# adapter.net
KiCad netlist of a schematic drawn in EAGLE
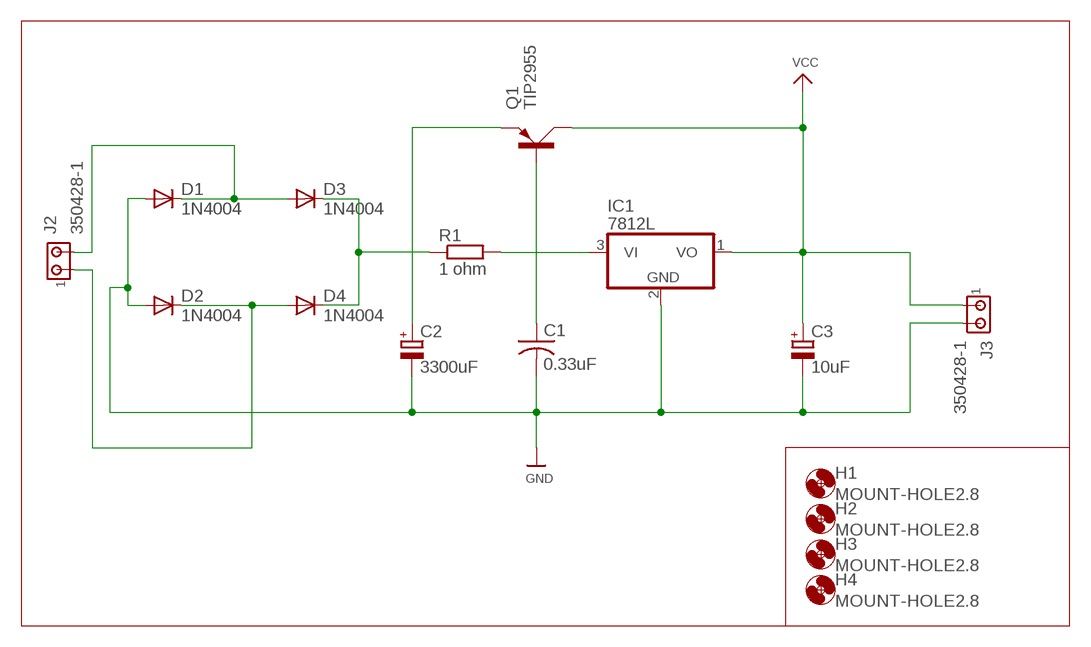
[diagram p0: schematic, sheet 1]

(export (version "E")
  (design (tool "Eeschema 10.0.6"))
  (components
    (comp (ref "C1")
      (value "0.33uF")
      (footprint "eagle-import:C025-024X044")
      (libsource (lib "eagle-import") (part "C-US025-024X044"))
    )
    (comp (ref "C2")
      (value "3300uF")
      (footprint "eagle-import:CAPPRD508W65D1000H1100B")
      (libsource (lib "eagle-import") (part "C-POLRADIAL-11MM-DIA_"))
    )
    (comp (ref "C3")
      (value "10uF")
      (footprint "eagle-import:CAPPRD508W65D1000H1100B")
      (libsource (lib "eagle-import") (part "C-POLRADIAL-11MM-DIA_"))
    )
    (comp (ref "D1")
      (value "1N4004")
      (footprint "eagle-import:DO41-10")
      (libsource (lib "eagle-import") (part "1N4004"))
    )
    (comp (ref "D2")
      (value "1N4004")
      (footprint "eagle-import:DO41-10")
      (libsource (lib "eagle-import") (part "1N4004"))
    )
    (comp (ref "D3")
      (value "1N4004")
      (footprint "eagle-import:DO41-10")
      (libsource (lib "eagle-import") (part "1N4004"))
    )
    (comp (ref "D4")
      (value "1N4004")
      (footprint "eagle-import:DO41-10")
      (libsource (lib "eagle-import") (part "1N4004"))
    )
    (comp (ref "H1")
      (value "MOUNT-HOLE2.8")
      (footprint "eagle-import:2,8")
      (libsource (lib "eagle-import") (part "MOUNT-HOLE2.8"))
    )
    (comp (ref "H2")
      (value "MOUNT-HOLE2.8")
      (footprint "eagle-import:2,8")
      (libsource (lib "eagle-import") (part "MOUNT-HOLE2.8"))
    )
    (comp (ref "H3")
      (value "MOUNT-HOLE2.8")
      (footprint "eagle-import:2,8")
      (libsource (lib "eagle-import") (part "MOUNT-HOLE2.8"))
    )
    (comp (ref "H4")
      (value "MOUNT-HOLE2.8")
      (footprint "eagle-import:2,8")
      (libsource (lib "eagle-import") (part "MOUNT-HOLE2.8"))
    )
    (comp (ref "IC1")
      (value "7812L")
      (footprint "eagle-import:TO92")
      (libsource (lib "eagle-import") (part "78L12"))
    )
    (comp (ref "J2")
      (value "350428-1")
      (footprint "eagle-import:350428-1")
      (libsource (lib "eagle-import") (part "350428-1"))
    )
    (comp (ref "J3")
      (value "350428-1")
      (footprint "eagle-import:350428-1")
      (libsource (lib "eagle-import") (part "350428-1"))
    )
    (comp (ref "Q1")
      (value "TIP2955")
      (footprint "eagle-import:TOP3AV")
      (fields (field (name "DIGIKEY_PART_NUMBER") "497-2608-5-ND") (field (name "MF") "STMicroelectronics"))
      (libsource (lib "eagle-import") (part "TIP2955"))
    )
    (comp (ref "R1")
      (value "1 ohm")
      (footprint "eagle-import:0204_7")
      (libsource (lib "eagle-import") (part "R-EU_0204/7"))
    )
  )
  (nets
    (net (code "1") (name "GND") (class "Default")
      (node (ref "C1") (pin "2") (pinfunction "2_2") (pintype "passive"))
      (node (ref "C2") (pin "2") (pinfunction "-_2") (pintype "passive"))
      (node (ref "C3") (pin "2") (pinfunction "-_2") (pintype "passive"))
      (node (ref "D1") (pin "A") (pinfunction "A_A") (pintype "passive"))
      (node (ref "D2") (pin "A") (pinfunction "A_A") (pintype "passive"))
      (node (ref "IC1") (pin "2") (pinfunction "GND_2") (pintype "passive"))
      (node (ref "J3") (pin "2") (pinfunction "2_2") (pintype "passive"))
    )
    (net (code "2") (name "Net-(C1-Pad1)") (class "Default")
      (node (ref "C1") (pin "1") (pinfunction "1_1") (pintype "passive"))
      (node (ref "Q1") (pin "B") (pinfunction "B_B") (pintype "passive"))
    )
    (net (code "3") (name "Net-(C2-+)") (class "Default")
      (node (ref "C2") (pin "1") (pinfunction "+_1") (pintype "passive"))
      (node (ref "Q1") (pin "E") (pinfunction "E_E") (pintype "passive"))
    )
    (net (code "4") (name "Net-(D1-PadC)") (class "Default")
      (node (ref "D1") (pin "C") (pinfunction "C_C") (pintype "passive"))
      (node (ref "D3") (pin "A") (pinfunction "A_A") (pintype "passive"))
      (node (ref "J2") (pin "2") (pinfunction "2_2") (pintype "passive"))
    )
    (net (code "5") (name "Net-(D2-PadC)") (class "Default")
      (node (ref "D2") (pin "C") (pinfunction "C_C") (pintype "passive"))
      (node (ref "D4") (pin "A") (pinfunction "A_A") (pintype "passive"))
      (node (ref "J2") (pin "1") (pinfunction "1_1") (pintype "passive"))
    )
    (net (code "6") (name "Net-(D3-PadC)") (class "Default")
      (node (ref "D3") (pin "C") (pinfunction "C_C") (pintype "passive"))
      (node (ref "D4") (pin "C") (pinfunction "C_C") (pintype "passive"))
      (node (ref "R1") (pin "1") (pinfunction "1_1") (pintype "passive"))
    )
    (net (code "7") (name "Net-(IC1-VI)") (class "Default")
      (node (ref "IC1") (pin "3") (pinfunction "VI_3") (pintype "input"))
      (node (ref "R1") (pin "2") (pinfunction "2_2") (pintype "passive"))
    )
    (net (code "8") (name "VCC") (class "Default")
      (node (ref "C3") (pin "1") (pinfunction "+_1") (pintype "passive"))
      (node (ref "IC1") (pin "1") (pinfunction "VO_1") (pintype "passive"))
      (node (ref "J3") (pin "1") (pinfunction "1_1") (pintype "passive"))
      (node (ref "Q1") (pin "C") (pinfunction "C_C") (pintype "passive"))
    )
  )
)
